# mag_pos.net
KiCad netlist of a schematic drawn in Altium Designer
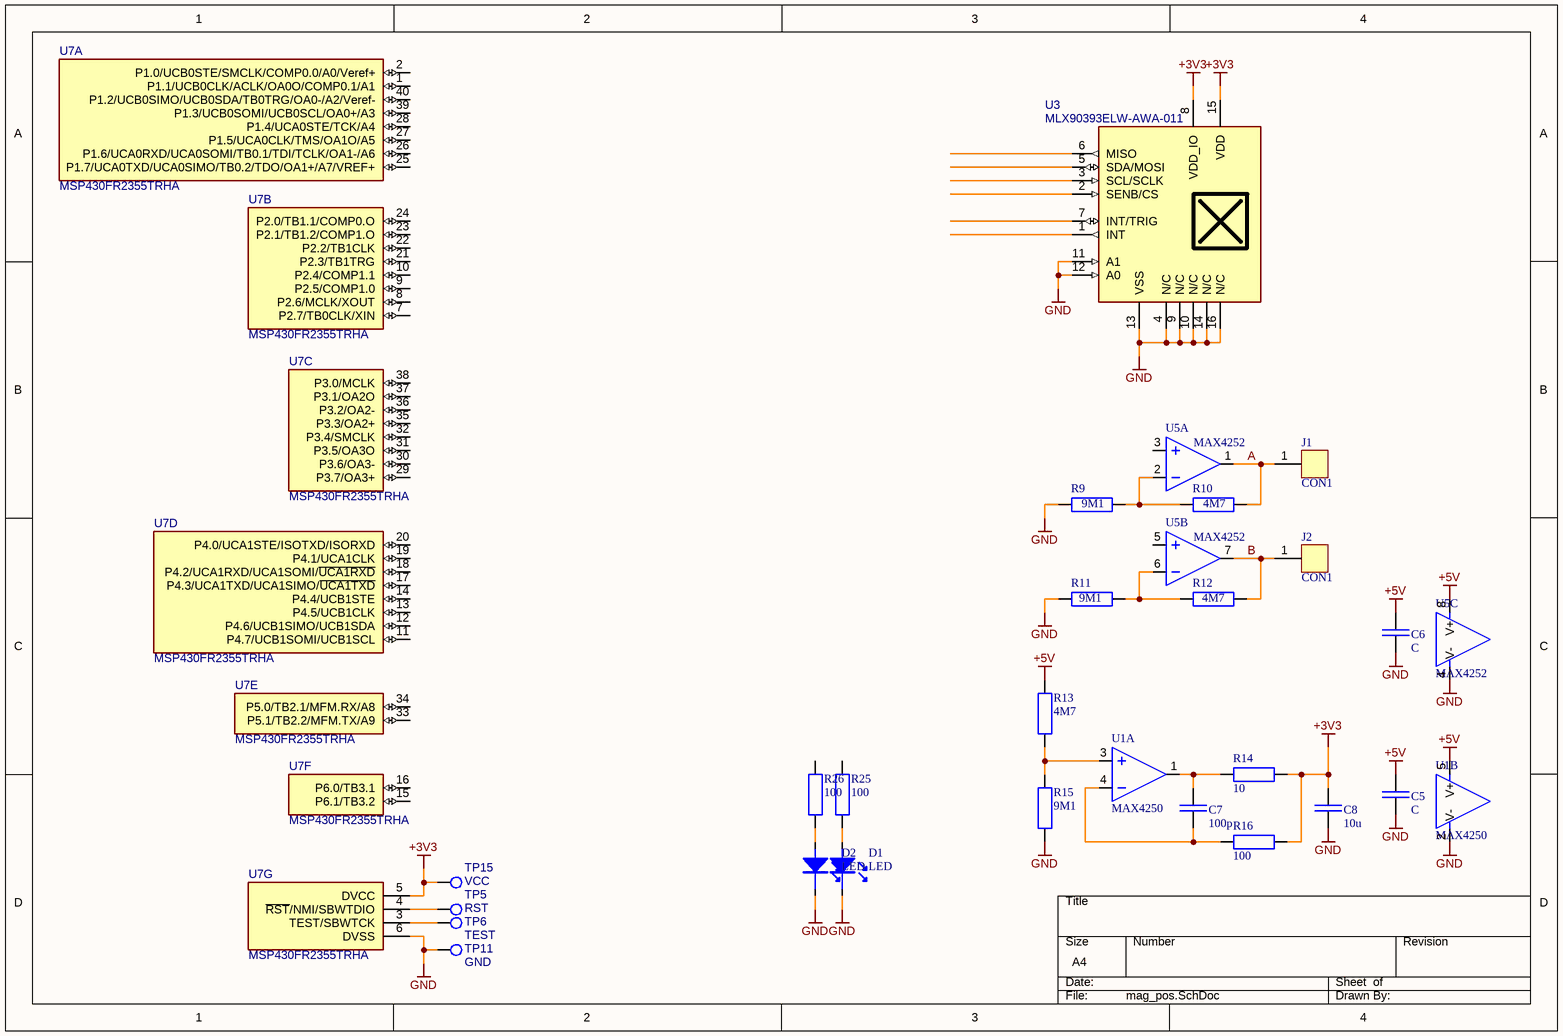
[diagram p0: mag_pos.SchDoc]

(export (version "E")
  (design (tool "Eeschema 10.0.6"))
  (components
    (comp (ref "C5")
      (value "C")
      (footprint "AHO_Altium_Lib:C_0603_S")
      (libsource (lib "AHO_Altium_Lib") (part "C"))
    )
    (comp (ref "C6")
      (value "C")
      (footprint "AHO_Altium_Lib:C_0603_S")
      (libsource (lib "AHO_Altium_Lib") (part "C"))
    )
    (comp (ref "C7")
      (value "100p")
      (footprint "AHO_Altium_Lib:C_0603_S")
      (libsource (lib "AHO_Altium_Lib") (part "C"))
    )
    (comp (ref "C8")
      (value "10u")
      (footprint "AHO_Altium_Lib:C_0805_S")
      (libsource (lib "AHO_Altium_Lib") (part "C"))
    )
    (comp (ref "D1")
      (value "LED")
      (footprint "LED_0603_S_BLUE")
      (libsource (lib "AHO_Altium_Lib") (part "LED"))
    )
    (comp (ref "D2")
      (value "LED")
      (footprint "LED_0603_S_GREEN")
      (libsource (lib "AHO_Altium_Lib") (part "LED"))
    )
    (comp (ref "J1")
      (value "CON1")
      (footprint "AHO_Altium_Lib:CON_1x1_tht_BMS")
      (libsource (lib "AHO_Altium_Lib") (part "CON1"))
    )
    (comp (ref "J2")
      (value "CON1")
      (footprint "AHO_Altium_Lib:CON_1x1_tht_BMS")
      (libsource (lib "AHO_Altium_Lib") (part "CON1"))
    )
    (comp (ref "R9")
      (value "9M1")
      (footprint "AHO_Altium_Lib:R_0603_S")
      (description "Normaler Widerstand")
      (libsource (lib "AHO_Altium_Lib") (part "R"))
    )
    (comp (ref "R10")
      (value "4M7")
      (footprint "AHO_Altium_Lib:R_0603_S")
      (description "Normaler Widerstand")
      (libsource (lib "AHO_Altium_Lib") (part "R"))
    )
    (comp (ref "R11")
      (value "9M1")
      (footprint "AHO_Altium_Lib:R_0603_S")
      (description "Normaler Widerstand")
      (libsource (lib "AHO_Altium_Lib") (part "R"))
    )
    (comp (ref "R12")
      (value "4M7")
      (footprint "AHO_Altium_Lib:R_0603_S")
      (description "Normaler Widerstand")
      (libsource (lib "AHO_Altium_Lib") (part "R"))
    )
    (comp (ref "R13")
      (value "4M7")
      (footprint "AHO_Altium_Lib:R_0603_S")
      (description "Normaler Widerstand")
      (libsource (lib "AHO_Altium_Lib") (part "R"))
    )
    (comp (ref "R14")
      (value "10")
      (footprint "AHO_Altium_Lib:R_0603_S")
      (description "Normaler Widerstand")
      (libsource (lib "AHO_Altium_Lib") (part "R"))
    )
    (comp (ref "R15")
      (value "9M1")
      (footprint "AHO_Altium_Lib:R_0603_S")
      (description "Normaler Widerstand")
      (libsource (lib "AHO_Altium_Lib") (part "R"))
    )
    (comp (ref "R16")
      (value "100")
      (footprint "AHO_Altium_Lib:R_0603_S")
      (description "Normaler Widerstand")
      (libsource (lib "AHO_Altium_Lib") (part "R"))
    )
    (comp (ref "R25")
      (value "100")
      (footprint "AHO_Altium_Lib:R_0603_S")
      (description "Normaler Widerstand")
      (libsource (lib "AHO_Altium_Lib") (part "R"))
    )
    (comp (ref "R26")
      (value "100")
      (footprint "AHO_Altium_Lib:R_0603_S")
      (description "Normaler Widerstand")
      (libsource (lib "AHO_Altium_Lib") (part "R"))
    )
    (comp (ref "TP5")
      (value "RST")
      (footprint "mag_pos:TP_SMD_1MM")
      (description "Testpoint SMD 1mm")
      (libsource (lib "mag_pos") (part "TP_SMD_1mm"))
    )
    (comp (ref "TP6")
      (value "TEST")
      (footprint "mag_pos:TP_SMD_1MM")
      (description "Testpoint SMD 1mm")
      (libsource (lib "mag_pos") (part "TP_SMD_1mm"))
    )
    (comp (ref "TP11")
      (value "GND")
      (footprint "mag_pos:TP_SMD_1MM")
      (description "Testpoint SMD 1mm")
      (libsource (lib "mag_pos") (part "TP_SMD_1mm"))
    )
    (comp (ref "TP15")
      (value "VCC")
      (footprint "mag_pos:TP_SMD_1MM")
      (description "Testpoint SMD 1mm")
      (libsource (lib "mag_pos") (part "TP_SMD_1mm"))
    )
    (comp (ref "U1")
      (value "MAX4250")
      (footprint "AHO_Altium_Lib:SOT23-5")
      (libsource (lib "AHO_Altium_Lib") (part "MAX4250"))
    )
    (comp (ref "U3")
      (value "MLX90393ELW-AWA-011")
      (footprint "mag_pos:QFN50P300X300X100-16")
      (description "Triaxis Magnetic Node, QFN16")
      (libsource (lib "mag_pos") (part "MLX90393ELW-AWA-011"))
    )
    (comp (ref "U5")
      (value "MAX4252")
      (footprint "AHO_Altium_Lib:DGK-8")
      (libsource (lib "AHO_Altium_Lib") (part "MAX4252"))
    )
    (comp (ref "U7")
      (value "MSP430FR2355TRHA")
      (footprint "mag_pos:QFN50P600X600X100-40")
      (description "Mixed-Signal Microcontroller, 16Bit, 32kB FRAM, 4kB SRAM, QFN40")
      (libsource (lib "mag_pos") (part "MSP430FR2355TRHA"))
    )
  )
  (nets
    (net (code "1") (name "+3V3") (class "Default")
      (node (ref "C8") (pin "1") (pinfunction "1_1") (pintype "passive"))
      (node (ref "R14") (pin "2") (pintype "passive"))
      (node (ref "R16") (pin "2") (pintype "passive"))
      (node (ref "TP15") (pin "1") (pinfunction "1_1") (pintype "passive"))
      (node (ref "U3") (pin "15") (pinfunction "VDD_15") (pintype "power_in"))
      (node (ref "U3") (pin "8") (pinfunction "VDD_IO_8") (pintype "power_in"))
      (node (ref "U7") (pin "5") (pinfunction "DVCC_5") (pintype "power_in"))
    )
    (net (code "2") (name "+5V") (class "Default")
      (node (ref "C5") (pin "1") (pinfunction "1_1") (pintype "passive"))
      (node (ref "C6") (pin "1") (pinfunction "1_1") (pintype "passive"))
      (node (ref "R13") (pin "1") (pintype "passive"))
      (node (ref "U1") (pin "5") (pinfunction "V+_5") (pintype "passive"))
      (node (ref "U5") (pin "8") (pinfunction "V+_8") (pintype "passive"))
    )
    (net (code "3") (name "/A") (class "Default")
      (node (ref "J1") (pin "1") (pintype "passive"))
      (node (ref "R10") (pin "1") (pintype "passive"))
      (node (ref "U5") (pin "1") (pinfunction "Out_D_1") (pintype "passive"))
    )
    (net (code "4") (name "/B") (class "Default")
      (node (ref "J2") (pin "1") (pintype "passive"))
      (node (ref "R12") (pin "1") (pintype "passive"))
      (node (ref "U5") (pin "7") (pinfunction "Out_D_7") (pintype "passive"))
    )
    (net (code "5") (name "GND") (class "Default")
      (node (ref "C5") (pin "2") (pinfunction "2_2") (pintype "passive"))
      (node (ref "C6") (pin "2") (pinfunction "2_2") (pintype "passive"))
      (node (ref "C8") (pin "2") (pinfunction "2_2") (pintype "passive"))
      (node (ref "D1") (pin "K") (pinfunction "K_K") (pintype "passive"))
      (node (ref "D2") (pin "K") (pinfunction "K_K") (pintype "passive"))
      (node (ref "R11") (pin "2") (pintype "passive"))
      (node (ref "R15") (pin "2") (pintype "passive"))
      (node (ref "R9") (pin "2") (pintype "passive"))
      (node (ref "TP11") (pin "1") (pinfunction "1_1") (pintype "passive"))
      (node (ref "U1") (pin "2") (pinfunction "V-_2") (pintype "passive"))
      (node (ref "U3") (pin "10") (pinfunction "N/C_10") (pintype "passive"))
      (node (ref "U3") (pin "11") (pinfunction "A1_11") (pintype "input"))
      (node (ref "U3") (pin "12") (pinfunction "A0_12") (pintype "input"))
      (node (ref "U3") (pin "13") (pinfunction "VSS_13") (pintype "power_in"))
      (node (ref "U3") (pin "14") (pinfunction "N/C_14") (pintype "passive"))
      (node (ref "U3") (pin "16") (pinfunction "N/C_16") (pintype "passive"))
      (node (ref "U3") (pin "4") (pinfunction "N/C_4") (pintype "passive"))
      (node (ref "U3") (pin "9") (pinfunction "N/C_9") (pintype "passive"))
      (node (ref "U5") (pin "4") (pinfunction "V-_4") (pintype "passive"))
      (node (ref "U7") (pin "6") (pinfunction "DVSS_6") (pintype "power_in"))
    )
    (net (code "6") (name "Net-(D1-PadA)") (class "Default")
      (node (ref "D1") (pin "A") (pinfunction "A_A") (pintype "passive"))
      (node (ref "R25") (pin "1") (pintype "passive"))
    )
    (net (code "7") (name "Net-(D2-PadA)") (class "Default")
      (node (ref "D2") (pin "A") (pinfunction "A_A") (pintype "passive"))
      (node (ref "R26") (pin "1") (pintype "passive"))
    )
    (net (code "8") (name "Net-(U1A-+In_D)") (class "Default")
      (node (ref "R13") (pin "2") (pintype "passive"))
      (node (ref "R15") (pin "1") (pintype "passive"))
      (node (ref "U1") (pin "3") (pinfunction "+In_D_3") (pintype "passive"))
    )
    (net (code "9") (name "Net-(U1A--In_D)") (class "Default")
      (node (ref "C7") (pin "2") (pinfunction "2_2") (pintype "passive"))
      (node (ref "R16") (pin "1") (pintype "passive"))
      (node (ref "U1") (pin "4") (pinfunction "-In_D_4") (pintype "passive"))
    )
    (net (code "10") (name "Net-(U1A-Out_D)") (class "Default")
      (node (ref "C7") (pin "1") (pinfunction "1_1") (pintype "passive"))
      (node (ref "R14") (pin "1") (pintype "passive"))
      (node (ref "U1") (pin "1") (pinfunction "Out_D_1") (pintype "passive"))
    )
    (net (code "11") (name "Net-(U5A--In_D)") (class "Default")
      (node (ref "R10") (pin "2") (pintype "passive"))
      (node (ref "R9") (pin "1") (pintype "passive"))
      (node (ref "U5") (pin "2") (pinfunction "-In_D_2") (pintype "passive"))
    )
    (net (code "12") (name "Net-(U5B--In_D)") (class "Default")
      (node (ref "R11") (pin "1") (pintype "passive"))
      (node (ref "R12") (pin "2") (pintype "passive"))
      (node (ref "U5") (pin "6") (pinfunction "-In_D_6") (pintype "passive"))
    )
    (net (code "13") (name "Net-(U7G-TEST{slash}SBWTCK)") (class "Default")
      (node (ref "TP6") (pin "1") (pinfunction "1_1") (pintype "passive"))
      (node (ref "U7") (pin "3") (pinfunction "TEST/SBWTCK_3") (pintype "power_in"))
    )
    (net (code "14") (name "Net-(U7G-~{RST}{slash}NMI{slash}SBWTDIO)") (class "Default")
      (node (ref "TP5") (pin "1") (pinfunction "1_1") (pintype "passive"))
      (node (ref "U7") (pin "4") (pinfunction "~{RST}/NMI/SBWTDIO_4") (pintype "power_in"))
    )
    (net (code "15") (name "unconnected-(R25-Pad2)") (class "Default")
      (node (ref "R25") (pin "2") (pintype "passive"))
    )
    (net (code "16") (name "unconnected-(R26-Pad2)") (class "Default")
      (node (ref "R26") (pin "2") (pintype "passive"))
    )
    (net (code "17") (name "unconnected-(U3-INT-Pad1)") (class "Default")
      (node (ref "U3") (pin "1") (pinfunction "INT_1") (pintype "output"))
    )
    (net (code "18") (name "unconnected-(U3-INT{slash}TRIG-Pad7)") (class "Default")
      (node (ref "U3") (pin "7") (pinfunction "INT/TRIG_7") (pintype "bidirectional"))
    )
    (net (code "19") (name "unconnected-(U3-MISO-Pad6)") (class "Default")
      (node (ref "U3") (pin "6") (pinfunction "MISO_6") (pintype "output"))
    )
    (net (code "20") (name "unconnected-(U3-SCL{slash}SCLK-Pad3)") (class "Default")
      (node (ref "U3") (pin "3") (pinfunction "SCL/SCLK_3") (pintype "input"))
    )
    (net (code "21") (name "unconnected-(U3-SDA{slash}MOSI-Pad5)") (class "Default")
      (node (ref "U3") (pin "5") (pinfunction "SDA/MOSI_5") (pintype "bidirectional"))
    )
    (net (code "22") (name "unconnected-(U3-SENB{slash}CS-Pad2)") (class "Default")
      (node (ref "U3") (pin "2") (pinfunction "SENB/CS_2") (pintype "input"))
    )
    (net (code "23") (name "unconnected-(U5A-+In_D-Pad3)") (class "Default")
      (node (ref "U5") (pin "3") (pinfunction "+In_D_3") (pintype "passive"))
    )
    (net (code "24") (name "unconnected-(U5B-+In_D-Pad5)") (class "Default")
      (node (ref "U5") (pin "5") (pinfunction "+In_D_5") (pintype "passive"))
    )
    (net (code "25") (name "unconnected-(U7A-P1.0{slash}UCB0STE{slash}SMCLK{slash}COMP0.0{slash}A0{slash}Veref+-Pad2)") (class "Default")
      (node (ref "U7") (pin "2") (pinfunction "P1.0/UCB0STE/SMCLK/COMP0.0/A0/Veref+_2") (pintype "bidirectional"))
    )
    (net (code "26") (name "unconnected-(U7A-P1.1{slash}UCB0CLK{slash}ACLK{slash}OA0O{slash}COMP0.1{slash}A1-Pad1)") (class "Default")
      (node (ref "U7") (pin "1") (pinfunction "P1.1/UCB0CLK/ACLK/OA0O/COMP0.1/A1_1") (pintype "bidirectional"))
    )
    (net (code "27") (name "unconnected-(U7A-P1.2{slash}UCB0SIMO{slash}UCB0SDA{slash}TB0TRG{slash}OA0-{slash}A2{slash}Veref--Pad40)") (class "Default")
      (node (ref "U7") (pin "40") (pinfunction "P1.2/UCB0SIMO/UCB0SDA/TB0TRG/OA0-/A2/Veref-_40") (pintype "bidirectional"))
    )
    (net (code "28") (name "unconnected-(U7A-P1.3{slash}UCB0SOMI{slash}UCB0SCL{slash}OA0+{slash}A3-Pad39)") (class "Default")
      (node (ref "U7") (pin "39") (pinfunction "P1.3/UCB0SOMI/UCB0SCL/OA0+/A3_39") (pintype "bidirectional"))
    )
    (net (code "29") (name "unconnected-(U7A-P1.4{slash}UCA0STE{slash}TCK{slash}A4-Pad28)") (class "Default")
      (node (ref "U7") (pin "28") (pinfunction "P1.4/UCA0STE/TCK/A4_28") (pintype "bidirectional"))
    )
    (net (code "30") (name "unconnected-(U7A-P1.5{slash}UCA0CLK{slash}TMS{slash}OA1O{slash}A5-Pad27)") (class "Default")
      (node (ref "U7") (pin "27") (pinfunction "P1.5/UCA0CLK/TMS/OA1O/A5_27") (pintype "bidirectional"))
    )
    (net (code "31") (name "unconnected-(U7A-P1.6{slash}UCA0RXD{slash}UCA0SOMI{slash}TB0.1{slash}TDI{slash}TCLK{slash}OA1-{slash}A6-Pad26)") (class "Default")
      (node (ref "U7") (pin "26") (pinfunction "P1.6/UCA0RXD/UCA0SOMI/TB0.1/TDI/TCLK/OA1-/A6_26") (pintype "bidirectional"))
    )
    (net (code "32") (name "unconnected-(U7A-P1.7{slash}UCA0TXD{slash}UCA0SIMO{slash}TB0.2{slash}TDO{slash}OA1+{slash}A7{slash}VREF+-Pad25)") (class "Default")
      (node (ref "U7") (pin "25") (pinfunction "P1.7/UCA0TXD/UCA0SIMO/TB0.2/TDO/OA1+/A7/VREF+_25") (pintype "bidirectional"))
    )
    (net (code "33") (name "unconnected-(U7B-P2.0{slash}TB1.1{slash}COMP0.O-Pad24)") (class "Default")
      (node (ref "U7") (pin "24") (pinfunction "P2.0/TB1.1/COMP0.O_24") (pintype "bidirectional"))
    )
    (net (code "34") (name "unconnected-(U7B-P2.1{slash}TB1.2{slash}COMP1.O-Pad23)") (class "Default")
      (node (ref "U7") (pin "23") (pinfunction "P2.1/TB1.2/COMP1.O_23") (pintype "bidirectional"))
    )
    (net (code "35") (name "unconnected-(U7B-P2.2{slash}TB1CLK-Pad22)") (class "Default")
      (node (ref "U7") (pin "22") (pinfunction "P2.2/TB1CLK_22") (pintype "bidirectional"))
    )
    (net (code "36") (name "unconnected-(U7B-P2.3{slash}TB1TRG-Pad21)") (class "Default")
      (node (ref "U7") (pin "21") (pinfunction "P2.3/TB1TRG_21") (pintype "bidirectional"))
    )
    (net (code "37") (name "unconnected-(U7B-P2.4{slash}COMP1.1-Pad10)") (class "Default")
      (node (ref "U7") (pin "10") (pinfunction "P2.4/COMP1.1_10") (pintype "bidirectional"))
    )
    (net (code "38") (name "unconnected-(U7B-P2.5{slash}COMP1.0-Pad9)") (class "Default")
      (node (ref "U7") (pin "9") (pinfunction "P2.5/COMP1.0_9") (pintype "bidirectional"))
    )
    (net (code "39") (name "unconnected-(U7B-P2.6{slash}MCLK{slash}XOUT-Pad8)") (class "Default")
      (node (ref "U7") (pin "8") (pinfunction "P2.6/MCLK/XOUT_8") (pintype "bidirectional"))
    )
    (net (code "40") (name "unconnected-(U7B-P2.7{slash}TB0CLK{slash}XIN-Pad7)") (class "Default")
      (node (ref "U7") (pin "7") (pinfunction "P2.7/TB0CLK/XIN_7") (pintype "bidirectional"))
    )
    (net (code "41") (name "unconnected-(U7C-P3.0{slash}MCLK-Pad38)") (class "Default")
      (node (ref "U7") (pin "38") (pinfunction "P3.0/MCLK_38") (pintype "bidirectional"))
    )
    (net (code "42") (name "unconnected-(U7C-P3.1{slash}OA2O-Pad37)") (class "Default")
      (node (ref "U7") (pin "37") (pinfunction "P3.1/OA2O_37") (pintype "bidirectional"))
    )
    (net (code "43") (name "unconnected-(U7C-P3.2{slash}OA2--Pad36)") (class "Default")
      (node (ref "U7") (pin "36") (pinfunction "P3.2/OA2-_36") (pintype "bidirectional"))
    )
    (net (code "44") (name "unconnected-(U7C-P3.3{slash}OA2+-Pad35)") (class "Default")
      (node (ref "U7") (pin "35") (pinfunction "P3.3/OA2+_35") (pintype "bidirectional"))
    )
    (net (code "45") (name "unconnected-(U7C-P3.4{slash}SMCLK-Pad32)") (class "Default")
      (node (ref "U7") (pin "32") (pinfunction "P3.4/SMCLK_32") (pintype "bidirectional"))
    )
    (net (code "46") (name "unconnected-(U7C-P3.5{slash}OA3O-Pad31)") (class "Default")
      (node (ref "U7") (pin "31") (pinfunction "P3.5/OA3O_31") (pintype "bidirectional"))
    )
    (net (code "47") (name "unconnected-(U7C-P3.6{slash}OA3--Pad30)") (class "Default")
      (node (ref "U7") (pin "30") (pinfunction "P3.6/OA3-_30") (pintype "bidirectional"))
    )
    (net (code "48") (name "unconnected-(U7C-P3.7{slash}OA3+-Pad29)") (class "Default")
      (node (ref "U7") (pin "29") (pinfunction "P3.7/OA3+_29") (pintype "bidirectional"))
    )
    (net (code "49") (name "unconnected-(U7D-P4.0{slash}UCA1STE{slash}ISOTXD{slash}ISORXD-Pad20)") (class "Default")
      (node (ref "U7") (pin "20") (pinfunction "P4.0/UCA1STE/ISOTXD/ISORXD_20") (pintype "bidirectional"))
    )
    (net (code "50") (name "unconnected-(U7D-P4.1{slash}UCA1CLK-Pad19)") (class "Default")
      (node (ref "U7") (pin "19") (pinfunction "P4.1/UCA1CLK_19") (pintype "bidirectional"))
    )
    (net (code "51") (name "unconnected-(U7D-P4.2{slash}UCA1RXD{slash}UCA1SOMI{slash}~{UCA1RXD}-Pad18)") (class "Default")
      (node (ref "U7") (pin "18") (pinfunction "P4.2/UCA1RXD/UCA1SOMI/~{UCA1RXD}_18") (pintype "bidirectional"))
    )
    (net (code "52") (name "unconnected-(U7D-P4.3{slash}UCA1TXD{slash}UCA1SIMO{slash}~{UCA1TXD}-Pad17)") (class "Default")
      (node (ref "U7") (pin "17") (pinfunction "P4.3/UCA1TXD/UCA1SIMO/~{UCA1TXD}_17") (pintype "bidirectional"))
    )
    (net (code "53") (name "unconnected-(U7D-P4.4{slash}UCB1STE-Pad14)") (class "Default")
      (node (ref "U7") (pin "14") (pinfunction "P4.4/UCB1STE_14") (pintype "bidirectional"))
    )
    (net (code "54") (name "unconnected-(U7D-P4.5{slash}UCB1CLK-Pad13)") (class "Default")
      (node (ref "U7") (pin "13") (pinfunction "P4.5/UCB1CLK_13") (pintype "bidirectional"))
    )
    (net (code "55") (name "unconnected-(U7D-P4.6{slash}UCB1SIMO{slash}UCB1SDA-Pad12)") (class "Default")
      (node (ref "U7") (pin "12") (pinfunction "P4.6/UCB1SIMO/UCB1SDA_12") (pintype "bidirectional"))
    )
    (net (code "56") (name "unconnected-(U7D-P4.7{slash}UCB1SOMI{slash}UCB1SCL-Pad11)") (class "Default")
      (node (ref "U7") (pin "11") (pinfunction "P4.7/UCB1SOMI/UCB1SCL_11") (pintype "bidirectional"))
    )
    (net (code "57") (name "unconnected-(U7E-P5.0{slash}TB2.1{slash}MFM.RX{slash}A8-Pad34)") (class "Default")
      (node (ref "U7") (pin "34") (pinfunction "P5.0/TB2.1/MFM.RX/A8_34") (pintype "bidirectional"))
    )
    (net (code "58") (name "unconnected-(U7E-P5.1{slash}TB2.2{slash}MFM.TX{slash}A9-Pad33)") (class "Default")
      (node (ref "U7") (pin "33") (pinfunction "P5.1/TB2.2/MFM.TX/A9_33") (pintype "bidirectional"))
    )
    (net (code "59") (name "unconnected-(U7F-P6.0{slash}TB3.1-Pad16)") (class "Default")
      (node (ref "U7") (pin "16") (pinfunction "P6.0/TB3.1_16") (pintype "bidirectional"))
    )
    (net (code "60") (name "unconnected-(U7F-P6.1{slash}TB3.2-Pad15)") (class "Default")
      (node (ref "U7") (pin "15") (pinfunction "P6.1/TB3.2_15") (pintype "bidirectional"))
    )
  )
)
